# ADC.net
KiCad netlist of a schematic drawn in Altium Designer
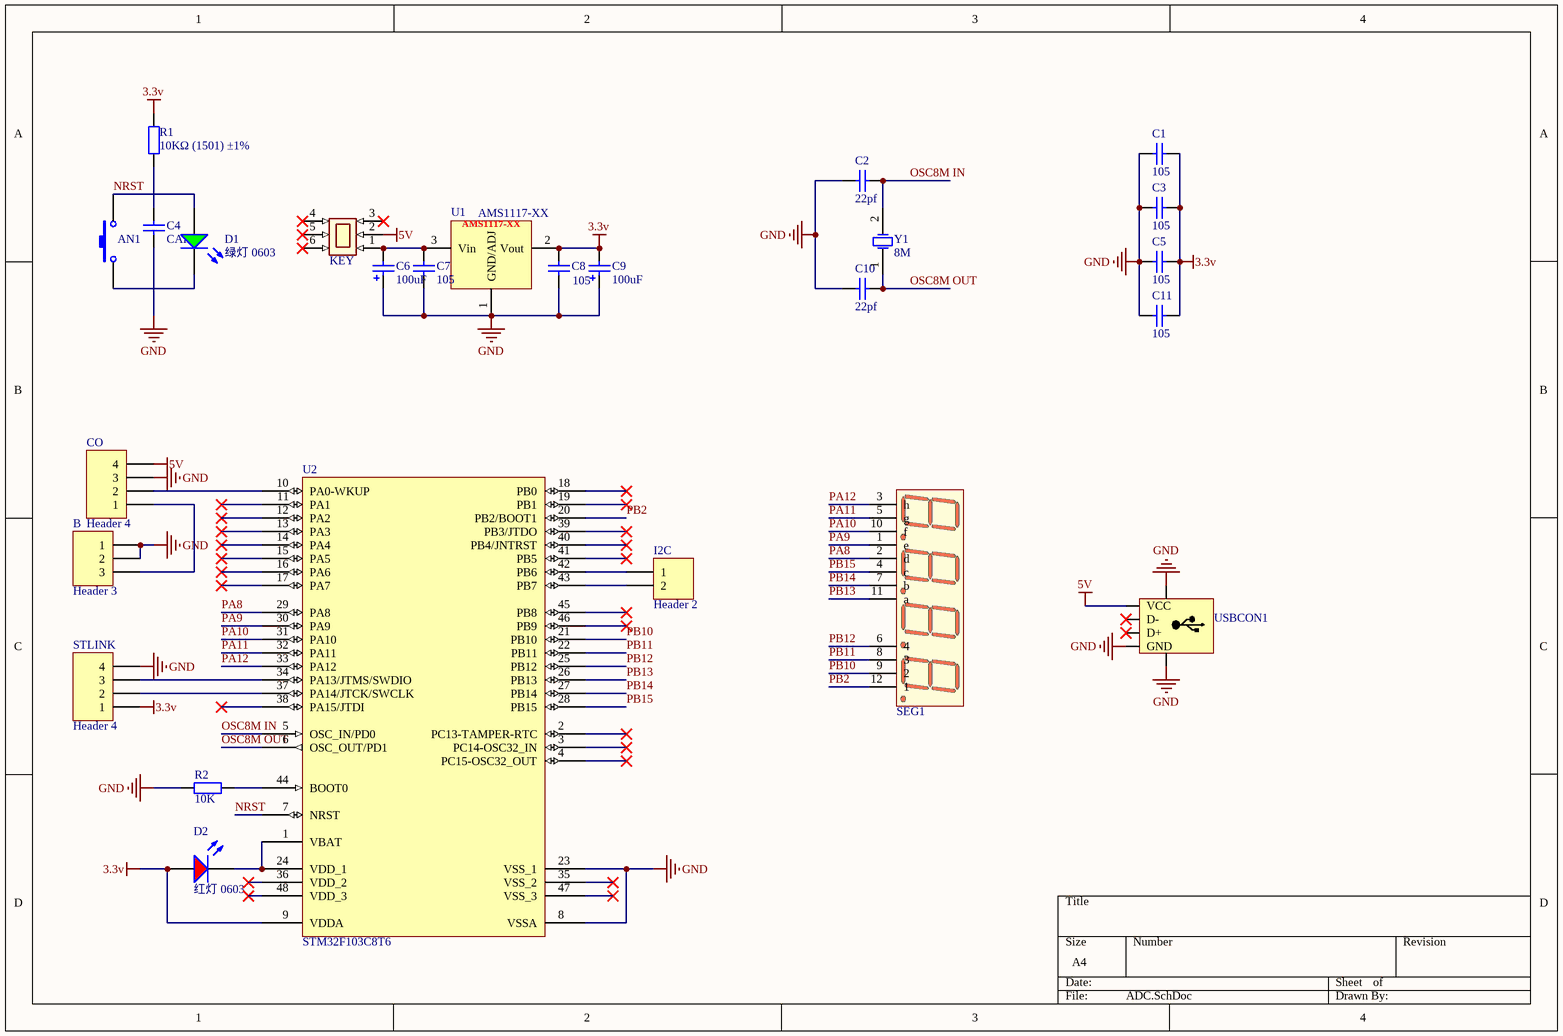
[diagram p0: ADC.SchDoc]

(export (version "E")
  (design (tool "Eeschema 10.0.6"))
  (components
    (comp (ref "AN1")
      (value "Button")
      (footprint "BUTTON-DIP")
      (fields (field (name "PUBLISHER") "Altium Limited"))
      (libsource (lib "开关按键器件") (part "Button"))
    )
    (comp (ref "B")
      (value "Header 3")
      (footprint "HDR1X3")
      (description "Header, 3-Pin")
      (fields (field (name "PUBLISHER") "Altium Limited"))
      (libsource (lib "连接器") (part "Header 3"))
    )
    (comp (ref "C1")
      (value "105")
      (footprint "C0603")
      (description "Polarized Capacitor (Radial)")
      (fields (field (name "Comment") "Cap Chip 0603") (field (name "PUBLISHER") "Altium Limited"))
      (libsource (lib "电容") (part "Cap Chip 0603"))
    )
    (comp (ref "C2")
      (value "22pf")
      (footprint "C0603")
      (description "Polarized Capacitor (Radial)")
      (fields (field (name "Comment") "Cap Chip 0603") (field (name "PUBLISHER") "Altium Limited"))
      (libsource (lib "电容") (part "Cap Chip 0603"))
    )
    (comp (ref "C3")
      (value "105")
      (footprint "C0603")
      (description "Polarized Capacitor (Radial)")
      (fields (field (name "Comment") "Cap Chip 0603") (field (name "PUBLISHER") "Altium Limited"))
      (libsource (lib "电容") (part "Cap Chip 0603"))
    )
    (comp (ref "C4")
      (value "CAP")
      (footprint "C0603")
      (description "Polarized Capacitor (Radial)")
      (fields (field (name "Comment") "Cap Chip 0603") (field (name "PUBLISHER") "Altium Limited"))
      (libsource (lib "电容") (part "Cap Chip 0603"))
    )
    (comp (ref "C5")
      (value "105")
      (footprint "C0603")
      (description "Polarized Capacitor (Radial)")
      (fields (field (name "Comment") "Cap Chip 0603") (field (name "PUBLISHER") "Altium Limited"))
      (libsource (lib "电容") (part "Cap Chip 0603"))
    )
    (comp (ref "C6")
      (value "100uF")
      (footprint "CAPPR2.5-6.3X11")
      (description "Polarized Capacitor (Radial)")
      (fields (field (name "Comment") "Cap Pol 2.5x6.3") (field (name "PUBLISHER") "Altium Limited"))
      (libsource (lib "电容") (part "Cap Pol 2.5x6.3"))
    )
    (comp (ref "C7")
      (value "105")
      (footprint "C0603")
      (description "Polarized Capacitor (Radial)")
      (fields (field (name "Comment") "Cap Chip 0603") (field (name "PUBLISHER") "Altium Limited"))
      (libsource (lib "电容") (part "Cap Chip 0603"))
    )
    (comp (ref "C8")
      (value "105")
      (footprint "C0603")
      (description "Polarized Capacitor (Radial)")
      (fields (field (name "Comment") "Cap Chip 0603") (field (name "PUBLISHER") "Altium Limited"))
      (libsource (lib "电容") (part "Cap Chip 0603"))
    )
    (comp (ref "C9")
      (value "100uF")
      (footprint "CAPPR2.5-6.3X11")
      (description "Polarized Capacitor (Radial)")
      (fields (field (name "Comment") "Cap Pol 2.5x6.3") (field (name "PUBLISHER") "Altium Limited"))
      (libsource (lib "电容") (part "Cap Pol 2.5x6.3"))
    )
    (comp (ref "C10")
      (value "22pf")
      (footprint "C0603")
      (description "Polarized Capacitor (Radial)")
      (fields (field (name "Comment") "Cap Chip 0603") (field (name "PUBLISHER") "Altium Limited"))
      (libsource (lib "电容") (part "Cap Chip 0603"))
    )
    (comp (ref "C11")
      (value "105")
      (footprint "C0603")
      (description "Polarized Capacitor (Radial)")
      (fields (field (name "Comment") "Cap Chip 0603") (field (name "PUBLISHER") "Altium Limited"))
      (libsource (lib "电容") (part "Cap Chip 0603"))
    )
    (comp (ref "CO")
      (value "Header 4")
      (footprint "HDR1X4")
      (description "Header, 4-Pin")
      (fields (field (name "PUBLISHER") "Altium Limited"))
      (libsource (lib "Miscellaneous Connectors") (part "Header 4"))
    )
    (comp (ref "D1")
      (value "绿灯 0603")
      (footprint "LC-0603_LED_S1")
      (description "发光二极管")
      (libsource (lib "Miscellaneous Devices LC") (part "0603 绿灯"))
    )
    (comp (ref "D2")
      (value "红灯 0603")
      (footprint "LC-0603_LED_S1")
      (description "发光二极管")
      (libsource (lib "Miscellaneous Devices LC") (part "0603 红灯"))
    )
    (comp (ref "I2C")
      (value "Header 2")
      (footprint "HDR1X2")
      (description "Header, 2-Pin")
      (fields (field (name "PUBLISHER") "Altium Limited"))
      (libsource (lib "连接器") (part "Header 2"))
    )
    (comp (ref "KEY") (value "开关(锁存开关）") (footprint "开关(锁存开关）") (libsource (lib "开关按键器件") (part "开关(锁存开关）")))
    (comp (ref "R1")
      (value "10KΩ (1501) ±1%")
      (footprint "LC-0402_R")
      (description "贴片电阻")
      (libsource (lib "Miscellaneous Devices LC") (part "0402 1.5KΩ (1501) 1%"))
    )
    (comp (ref "R2")
      (value "10K")
      (footprint "R0603")
      (description "Resistor")
      (fields (field (name "Comment") "Resistor Chip 0603") (field (name "PUBLISHER") "Altium Limited"))
      (libsource (lib "电阻") (part "Resistor Chip 0603"))
    )
    (comp (ref "SEG1")
      (value "R-G-B")
      (footprint "4-SEGMENTS")
      (description "4-BIT-SEGMENTS")
      (libsource (lib "光电显示器件") (part "4-SEGMENTS"))
    )
    (comp (ref "STLINK")
      (value "Header 4")
      (footprint "HDR1X4")
      (description "Header, 4-Pin")
      (fields (field (name "PUBLISHER") "Altium Limited"))
      (libsource (lib "Miscellaneous Connectors") (part "Header 4"))
    )
    (comp (ref "U1")
      (value "AMS1117-XX")
      (footprint "SOT-223-4")
      (description "AMS   800mA LOW DROPOUT VOLTAGE REGULATOR")
      (libsource (lib "电源ICs") (part "AMS1117-XX"))
    )
    (comp (ref "U2")
      (value "STM32F103C8T6")
      (footprint "LQFP48_N")
      (description "STM32 ARM-based 32-bit MCU with 64 Kbytes Flash, 48-pin LQFP, Industrial Temperature")
      (fields (field (name "PUBLISHER") "*"))
      (libsource (lib "The BeatlesIntegratedLibrary") (part "STM32F103C8T6"))
    )
    (comp (ref "USBCON1")
      (value "USB-4P")
      (footprint "USB-A")
      (description "USB CONNECTOR")
      (libsource (lib "连接器") (part "USB-4P"))
    )
    (comp (ref "Y1")
      (value "8M")
      (footprint "LC-SMD-5032_2P")
      (description "贴片晶振")
      (libsource (lib "Miscellaneous Devices LC") (part "SMD-5032_2P 8MHz 20ppm 20pF"))
    )
  )
  (nets
    (net (code "1") (name "/NRST") (class "Default")
      (node (ref "AN1") (pin "1") (pinfunction "1_1") (pintype "passive"))
      (node (ref "D1") (pin "A") (pinfunction "A_A") (pintype "passive"))
      (node (ref "U2") (pin "7") (pinfunction "NRST_7") (pintype "bidirectional"))
    )
    (net (code "2") (name "/OSC8M IN") (class "Default")
      (node (ref "C2") (pin "2") (pinfunction "2_2") (pintype "passive"))
      (node (ref "U2") (pin "5") (pinfunction "OSC_IN/PD0_5") (pintype "input"))
      (node (ref "Y1") (pin "2") (pinfunction "OSC2_2") (pintype "passive"))
    )
    (net (code "3") (name "/OSC8M OUT") (class "Default")
      (node (ref "C10") (pin "2") (pinfunction "2_2") (pintype "passive"))
      (node (ref "U2") (pin "6") (pinfunction "OSC_OUT/PD1_6") (pintype "output"))
      (node (ref "Y1") (pin "1") (pinfunction "OSC1_1") (pintype "passive"))
    )
    (net (code "4") (name "/PA8") (class "Default")
      (node (ref "SEG1") (pin "2") (pinfunction "d_2") (pintype "passive"))
      (node (ref "U2") (pin "29") (pinfunction "PA8_29") (pintype "bidirectional"))
    )
    (net (code "5") (name "/PA9") (class "Default")
      (node (ref "SEG1") (pin "1") (pinfunction "e_1") (pintype "passive"))
      (node (ref "U2") (pin "30") (pinfunction "PA9_30") (pintype "bidirectional"))
    )
    (net (code "6") (name "/PA10") (class "Default")
      (node (ref "SEG1") (pin "10") (pinfunction "f_10") (pintype "passive"))
      (node (ref "U2") (pin "31") (pinfunction "PA10_31") (pintype "bidirectional"))
    )
    (net (code "7") (name "/PA11") (class "Default")
      (node (ref "SEG1") (pin "5") (pinfunction "g_5") (pintype "passive"))
      (node (ref "U2") (pin "32") (pinfunction "PA11_32") (pintype "bidirectional"))
    )
    (net (code "8") (name "/PA12") (class "Default")
      (node (ref "SEG1") (pin "3") (pinfunction "h_3") (pintype "passive"))
      (node (ref "U2") (pin "33") (pinfunction "PA12_33") (pintype "bidirectional"))
    )
    (net (code "9") (name "/PB2") (class "Default")
      (node (ref "SEG1") (pin "12") (pinfunction "1_12") (pintype "passive"))
      (node (ref "U2") (pin "20") (pinfunction "PB2/BOOT1_20") (pintype "bidirectional"))
    )
    (net (code "10") (name "/PB10") (class "Default")
      (node (ref "SEG1") (pin "9") (pinfunction "2_9") (pintype "passive"))
      (node (ref "U2") (pin "21") (pinfunction "PB10_21") (pintype "bidirectional"))
    )
    (net (code "11") (name "/PB11") (class "Default")
      (node (ref "SEG1") (pin "8") (pinfunction "3_8") (pintype "passive"))
      (node (ref "U2") (pin "22") (pinfunction "PB11_22") (pintype "bidirectional"))
    )
    (net (code "12") (name "/PB12") (class "Default")
      (node (ref "SEG1") (pin "6") (pinfunction "4_6") (pintype "passive"))
      (node (ref "U2") (pin "25") (pinfunction "PB12_25") (pintype "bidirectional"))
    )
    (net (code "13") (name "/PB13") (class "Default")
      (node (ref "SEG1") (pin "11") (pinfunction "a_11") (pintype "passive"))
      (node (ref "U2") (pin "26") (pinfunction "PB13_26") (pintype "bidirectional"))
    )
    (net (code "14") (name "/PB14") (class "Default")
      (node (ref "SEG1") (pin "7") (pinfunction "b_7") (pintype "passive"))
      (node (ref "U2") (pin "27") (pinfunction "PB14_27") (pintype "bidirectional"))
    )
    (net (code "15") (name "/PB15") (class "Default")
      (node (ref "SEG1") (pin "4") (pinfunction "c_4") (pintype "passive"))
      (node (ref "U2") (pin "28") (pinfunction "PB15_28") (pintype "bidirectional"))
    )
    (net (code "16") (name "3.3v") (class "Default")
      (node (ref "C1") (pin "2") (pinfunction "2_2") (pintype "passive"))
      (node (ref "C11") (pin "2") (pinfunction "2_2") (pintype "passive"))
      (node (ref "C3") (pin "2") (pinfunction "2_2") (pintype "passive"))
      (node (ref "C5") (pin "2") (pinfunction "2_2") (pintype "passive"))
      (node (ref "C8") (pin "2") (pinfunction "2_2") (pintype "passive"))
      (node (ref "C9") (pin "2") (pinfunction "2_2") (pintype "passive"))
      (node (ref "D2") (pin "A") (pinfunction "A_A") (pintype "passive"))
      (node (ref "R1") (pin "2") (pinfunction "2_2") (pintype "passive"))
      (node (ref "STLINK") (pin "1") (pinfunction "1_1") (pintype "passive"))
      (node (ref "U1") (pin "2") (pinfunction "Vout_2") (pintype "passive"))
      (node (ref "U2") (pin "9") (pinfunction "VDDA_9") (pintype "power_in"))
    )
    (net (code "17") (name "5V") (class "Default")
      (node (ref "CO") (pin "4") (pinfunction "4_4") (pintype "passive"))
      (node (ref "KEY") (pin "2") (pinfunction "2_2") (pintype "input"))
      (node (ref "USBCON1") (pin "1") (pinfunction "VCC_1") (pintype "passive"))
    )
    (net (code "18") (name "GND") (class "Default")
      (node (ref "B") (pin "1") (pinfunction "1_1") (pintype "passive"))
      (node (ref "B") (pin "2") (pinfunction "2_2") (pintype "passive"))
      (node (ref "C1") (pin "1") (pinfunction "1_1") (pintype "passive"))
      (node (ref "C10") (pin "1") (pinfunction "1_1") (pintype "passive"))
      (node (ref "C11") (pin "1") (pinfunction "1_1") (pintype "passive"))
      (node (ref "C2") (pin "1") (pinfunction "1_1") (pintype "passive"))
      (node (ref "C3") (pin "1") (pinfunction "1_1") (pintype "passive"))
      (node (ref "C4") (pin "1") (pinfunction "1_1") (pintype "passive"))
      (node (ref "C5") (pin "1") (pinfunction "1_1") (pintype "passive"))
      (node (ref "C6") (pin "1") (pinfunction "1_1") (pintype "passive"))
      (node (ref "C7") (pin "1") (pinfunction "1_1") (pintype "passive"))
      (node (ref "C8") (pin "1") (pinfunction "1_1") (pintype "passive"))
      (node (ref "C9") (pin "1") (pinfunction "1_1") (pintype "passive"))
      (node (ref "CO") (pin "3") (pinfunction "3_3") (pintype "passive"))
      (node (ref "R2") (pin "1") (pinfunction "1_1") (pintype "passive"))
      (node (ref "STLINK") (pin "4") (pinfunction "4_4") (pintype "passive"))
      (node (ref "U1") (pin "1") (pinfunction "GND/ADJ_1") (pintype "passive"))
      (node (ref "U2") (pin "23") (pinfunction "VSS_1_23") (pintype "power_in"))
      (node (ref "U2") (pin "8") (pinfunction "VSSA_8") (pintype "power_in"))
      (node (ref "USBCON1") (pin "4") (pinfunction "GND_4") (pintype "passive"))
      (node (ref "USBCON1") (pin "5") (pinfunction "GND_5") (pintype "passive"))
      (node (ref "USBCON1") (pin "6") (pinfunction "GND_6") (pintype "passive"))
    )
    (net (code "19") (name "Net-(AN1-Pad2)") (class "Default")
      (node (ref "AN1") (pin "2") (pinfunction "2_2") (pintype "passive"))
      (node (ref "D1") (pin "K") (pinfunction "K_K") (pintype "passive"))
    )
    (net (code "20") (name "Net-(B-Pad3)") (class "Default")
      (node (ref "B") (pin "3") (pinfunction "3_3") (pintype "passive"))
      (node (ref "CO") (pin "1") (pinfunction "1_1") (pintype "passive"))
    )
    (net (code "21") (name "Net-(C4-Pad2)") (class "Default")
      (node (ref "C4") (pin "2") (pinfunction "2_2") (pintype "passive"))
      (node (ref "R1") (pin "1") (pinfunction "1_1") (pintype "passive"))
    )
    (net (code "22") (name "Net-(U1-Vin)") (class "Default")
      (node (ref "C6") (pin "2") (pinfunction "2_2") (pintype "passive"))
      (node (ref "C7") (pin "2") (pinfunction "2_2") (pintype "passive"))
      (node (ref "KEY") (pin "1") (pinfunction "1_1") (pintype "input"))
      (node (ref "U1") (pin "3") (pinfunction "Vin_3") (pintype "passive"))
    )
    (net (code "23") (name "Net-(U2-BOOT0)") (class "Default")
      (node (ref "R2") (pin "2") (pinfunction "2_2") (pintype "passive"))
      (node (ref "U2") (pin "44") (pinfunction "BOOT0_44") (pintype "input"))
    )
    (net (code "24") (name "Net-(U2-PA0-WKUP)") (class "Default")
      (node (ref "CO") (pin "2") (pinfunction "2_2") (pintype "passive"))
      (node (ref "U2") (pin "10") (pinfunction "PA0-WKUP_10") (pintype "bidirectional"))
    )
    (net (code "25") (name "Net-(U2-PA13{slash}JTMS{slash}SWDIO)") (class "Default")
      (node (ref "STLINK") (pin "3") (pinfunction "3_3") (pintype "passive"))
      (node (ref "U2") (pin "34") (pinfunction "PA13/JTMS/SWDIO_34") (pintype "bidirectional"))
    )
    (net (code "26") (name "Net-(U2-PA14{slash}JTCK{slash}SWCLK)") (class "Default")
      (node (ref "STLINK") (pin "2") (pinfunction "2_2") (pintype "passive"))
      (node (ref "U2") (pin "37") (pinfunction "PA14/JTCK/SWCLK_37") (pintype "bidirectional"))
    )
    (net (code "27") (name "Net-(U2-PB6)") (class "Default")
      (node (ref "I2C") (pin "1") (pinfunction "1_1") (pintype "passive"))
      (node (ref "U2") (pin "42") (pinfunction "PB6_42") (pintype "bidirectional"))
    )
    (net (code "28") (name "Net-(U2-PB7)") (class "Default")
      (node (ref "I2C") (pin "2") (pinfunction "2_2") (pintype "passive"))
      (node (ref "U2") (pin "43") (pinfunction "PB7_43") (pintype "bidirectional"))
    )
    (net (code "29") (name "Net-(U2-VBAT)") (class "Default")
      (node (ref "D2") (pin "K") (pinfunction "K_K") (pintype "passive"))
      (node (ref "U2") (pin "1") (pinfunction "VBAT_1") (pintype "power_in"))
      (node (ref "U2") (pin "24") (pinfunction "VDD_1_24") (pintype "power_in"))
    )
    (net (code "30") (name "unconnected-(KEY-Pad3)") (class "Default")
      (node (ref "KEY") (pin "3") (pinfunction "3_3") (pintype "input+no_connect"))
    )
    (net (code "31") (name "unconnected-(KEY-Pad4)") (class "Default")
      (node (ref "KEY") (pin "4") (pinfunction "4_4") (pintype "input+no_connect"))
    )
    (net (code "32") (name "unconnected-(KEY-Pad5)") (class "Default")
      (node (ref "KEY") (pin "5") (pinfunction "5_5") (pintype "input+no_connect"))
    )
    (net (code "33") (name "unconnected-(KEY-Pad6)") (class "Default")
      (node (ref "KEY") (pin "6") (pinfunction "6_6") (pintype "input+no_connect"))
    )
    (net (code "34") (name "unconnected-(U2-PA1-Pad11)") (class "Default")
      (node (ref "U2") (pin "11") (pinfunction "PA1_11") (pintype "bidirectional+no_connect"))
    )
    (net (code "35") (name "unconnected-(U2-PA2-Pad12)") (class "Default")
      (node (ref "U2") (pin "12") (pinfunction "PA2_12") (pintype "bidirectional+no_connect"))
    )
    (net (code "36") (name "unconnected-(U2-PA3-Pad13)") (class "Default")
      (node (ref "U2") (pin "13") (pinfunction "PA3_13") (pintype "bidirectional+no_connect"))
    )
    (net (code "37") (name "unconnected-(U2-PA4-Pad14)") (class "Default")
      (node (ref "U2") (pin "14") (pinfunction "PA4_14") (pintype "bidirectional+no_connect"))
    )
    (net (code "38") (name "unconnected-(U2-PA5-Pad15)") (class "Default")
      (node (ref "U2") (pin "15") (pinfunction "PA5_15") (pintype "bidirectional+no_connect"))
    )
    (net (code "39") (name "unconnected-(U2-PA6-Pad16)") (class "Default")
      (node (ref "U2") (pin "16") (pinfunction "PA6_16") (pintype "bidirectional+no_connect"))
    )
    (net (code "40") (name "unconnected-(U2-PA7-Pad17)") (class "Default")
      (node (ref "U2") (pin "17") (pinfunction "PA7_17") (pintype "bidirectional+no_connect"))
    )
    (net (code "41") (name "unconnected-(U2-PA15{slash}JTDI-Pad38)") (class "Default")
      (node (ref "U2") (pin "38") (pinfunction "PA15/JTDI_38") (pintype "bidirectional+no_connect"))
    )
    (net (code "42") (name "unconnected-(U2-PB0-Pad18)") (class "Default")
      (node (ref "U2") (pin "18") (pinfunction "PB0_18") (pintype "bidirectional+no_connect"))
    )
    (net (code "43") (name "unconnected-(U2-PB1-Pad19)") (class "Default")
      (node (ref "U2") (pin "19") (pinfunction "PB1_19") (pintype "bidirectional+no_connect"))
    )
    (net (code "44") (name "unconnected-(U2-PB3{slash}JTDO-Pad39)") (class "Default")
      (node (ref "U2") (pin "39") (pinfunction "PB3/JTDO_39") (pintype "bidirectional+no_connect"))
    )
    (net (code "45") (name "unconnected-(U2-PB4{slash}JNTRST-Pad40)") (class "Default")
      (node (ref "U2") (pin "40") (pinfunction "PB4/JNTRST_40") (pintype "bidirectional+no_connect"))
    )
    (net (code "46") (name "unconnected-(U2-PB5-Pad41)") (class "Default")
      (node (ref "U2") (pin "41") (pinfunction "PB5_41") (pintype "bidirectional+no_connect"))
    )
    (net (code "47") (name "unconnected-(U2-PB8-Pad45)") (class "Default")
      (node (ref "U2") (pin "45") (pinfunction "PB8_45") (pintype "bidirectional+no_connect"))
    )
    (net (code "48") (name "unconnected-(U2-PB9-Pad46)") (class "Default")
      (node (ref "U2") (pin "46") (pinfunction "PB9_46") (pintype "bidirectional+no_connect"))
    )
    (net (code "49") (name "unconnected-(U2-PC13-TAMPER-RTC-Pad2)") (class "Default")
      (node (ref "U2") (pin "2") (pinfunction "PC13-TAMPER-RTC_2") (pintype "bidirectional+no_connect"))
    )
    (net (code "50") (name "unconnected-(U2-PC14-OSC32_IN-Pad3)") (class "Default")
      (node (ref "U2") (pin "3") (pinfunction "PC14-OSC32_IN_3") (pintype "bidirectional+no_connect"))
    )
    (net (code "51") (name "unconnected-(U2-PC15-OSC32_OUT-Pad4)") (class "Default")
      (node (ref "U2") (pin "4") (pinfunction "PC15-OSC32_OUT_4") (pintype "bidirectional+no_connect"))
    )
    (net (code "52") (name "unconnected-(U2-VDD_2-Pad36)") (class "Default")
      (node (ref "U2") (pin "36") (pinfunction "VDD_2_36") (pintype "power_in+no_connect"))
    )
    (net (code "53") (name "unconnected-(U2-VDD_3-Pad48)") (class "Default")
      (node (ref "U2") (pin "48") (pinfunction "VDD_3_48") (pintype "power_in+no_connect"))
    )
    (net (code "54") (name "unconnected-(U2-VSS_2-Pad35)") (class "Default")
      (node (ref "U2") (pin "35") (pinfunction "VSS_2_35") (pintype "power_in+no_connect"))
    )
    (net (code "55") (name "unconnected-(U2-VSS_3-Pad47)") (class "Default")
      (node (ref "U2") (pin "47") (pinfunction "VSS_3_47") (pintype "power_in+no_connect"))
    )
    (net (code "56") (name "unconnected-(USBCON1-D+-Pad3)") (class "Default")
      (node (ref "USBCON1") (pin "3") (pinfunction "D+_3") (pintype "passive+no_connect"))
    )
    (net (code "57") (name "unconnected-(USBCON1-D--Pad2)") (class "Default")
      (node (ref "USBCON1") (pin "2") (pinfunction "D-_2") (pintype "passive+no_connect"))
    )
  )
)
